# relayboard_1.net
KiCad netlist of a schematic drawn in EAGLE
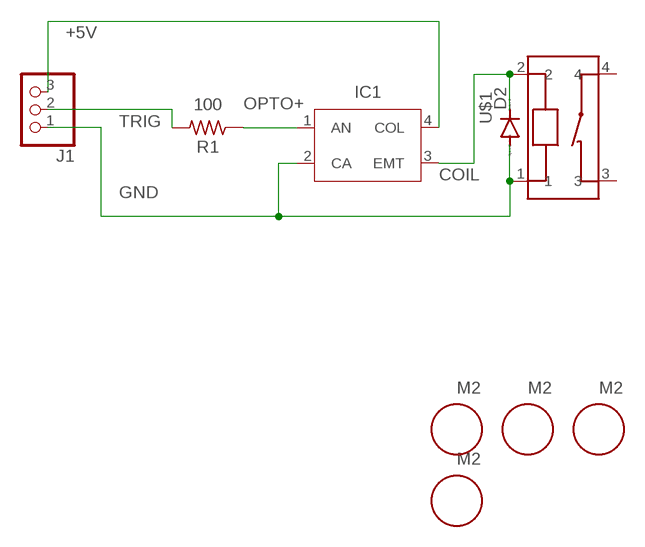
[diagram p0: schematic, sheet 1]

(export (version "E")
  (design (tool "Eeschema 10.0.6"))
  (components
    (comp (ref "D2")
      (value "1N4004")
      (footprint "eagle-import:DO41-10")
      (libsource (lib "eagle-import") (part "1N4004"))
    )
    (comp (ref "IC1")
      (value "FOD817BSDSMT")
      (footprint "eagle-import:DIP1016W60P279L460H460Q4B")
      (fields (field (name "MANUFACTURER") "ON Semiconductor") (field (name "MPN") "FOD817BSD"))
      (libsource (lib "eagle-import") (part "FOD817BSDSMT"))
    )
    (comp (ref "J1")
      (value "PINHD-1X3")
      (footprint "eagle-import:1X03")
      (libsource (lib "eagle-import") (part "PINHD-1X3"))
    )
    (comp (ref "R1")
      (value "100")
      (footprint "eagle-import:RESAD724W46L381D178B")
      (libsource (lib "eagle-import") (part "R-USAXIAL-7.2MM-PITCH_"))
    )
    (comp (ref "S1")
      (value "M2-POST")
      (footprint "eagle-import:M2-POST")
      (libsource (lib "eagle-import") (part "M2-POST"))
    )
    (comp (ref "U$1")
      (value "ALF1P05")
      (footprint "eagle-import:LF_1_FORM_A_PCB")
      (libsource (lib "eagle-import") (part "ALF1P05"))
    )
    (comp (ref "U$3")
      (value "M2-POST")
      (footprint "eagle-import:M2-POST")
      (libsource (lib "eagle-import") (part "M2-POST"))
    )
    (comp (ref "U$4")
      (value "M2-POST")
      (footprint "eagle-import:M2-POST")
      (libsource (lib "eagle-import") (part "M2-POST"))
    )
    (comp (ref "U$6")
      (value "M2-POST")
      (footprint "eagle-import:M2-POST")
      (libsource (lib "eagle-import") (part "M2-POST"))
    )
  )
  (nets
    (net (code "1") (name "/+5V") (class "Default")
      (node (ref "IC1") (pin "4") (pinfunction "COL_4") (pintype "input"))
      (node (ref "J1") (pin "3") (pinfunction "3_3") (pintype "passive"))
    )
    (net (code "2") (name "/COIL") (class "Default")
      (node (ref "D2") (pin "C") (pinfunction "C_C") (pintype "passive"))
      (node (ref "IC1") (pin "3") (pinfunction "EMT_3") (pintype "output"))
      (node (ref "U$1") (pin "2") (pinfunction "2_2") (pintype "bidirectional"))
    )
    (net (code "3") (name "/GND") (class "Default")
      (node (ref "D2") (pin "A") (pinfunction "A_A") (pintype "passive"))
      (node (ref "IC1") (pin "2") (pinfunction "CA_2") (pintype "bidirectional"))
      (node (ref "J1") (pin "1") (pinfunction "1_1") (pintype "passive"))
      (node (ref "U$1") (pin "1") (pinfunction "1_1") (pintype "bidirectional"))
    )
    (net (code "4") (name "/OPTO+") (class "Default")
      (node (ref "IC1") (pin "1") (pinfunction "AN_1") (pintype "bidirectional"))
      (node (ref "R1") (pin "1") (pinfunction "1_1") (pintype "passive"))
    )
    (net (code "5") (name "/TRIG") (class "Default")
      (node (ref "J1") (pin "2") (pinfunction "2_2") (pintype "passive"))
      (node (ref "R1") (pin "2") (pinfunction "2_2") (pintype "passive"))
    )
    (net (code "6") (name "unconnected-(U$1-Pad3)") (class "Default")
      (node (ref "U$1") (pin "3") (pinfunction "3_3") (pintype "bidirectional"))
    )
    (net (code "7") (name "unconnected-(U$1-Pad4)") (class "Default")
      (node (ref "U$1") (pin "4") (pinfunction "4_4") (pintype "bidirectional"))
    )
  )
)
